# Board_Kabin_shematic.net
KiCad netlist of a schematic drawn in Altium Designer
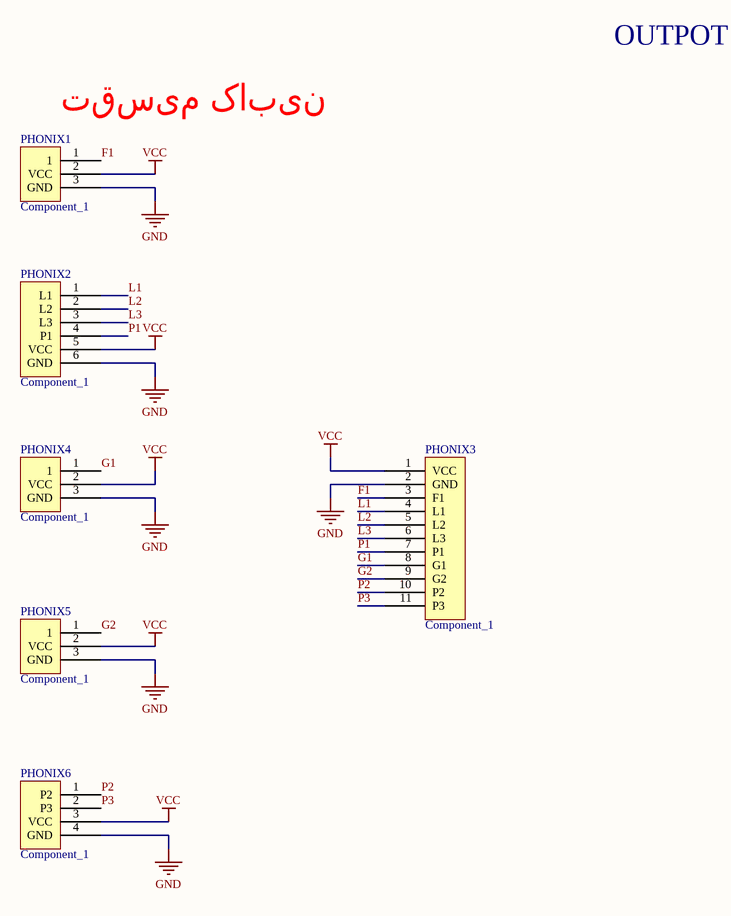
[diagram p0: Board_Kabin_shematic.SchDoc]

(export (version "E")
  (design (tool "Eeschema 10.0.6"))
  (components
    (comp (ref "PHONIX1")
      (value "Component_1")
      (footprint "PHONIX3")
      (description "PHONIX3PIN DIP")
      (libsource (lib "PHONIX3_SH") (part "Component_1"))
    )
    (comp (ref "PHONIX2")
      (value "Component_1")
      (footprint "PHONIX5")
      (libsource (lib "PHONIX6_SH") (part "Component_1"))
    )
    (comp (ref "PHONIX3")
      (value "Component_1")
      (footprint "PHONIX11")
      (description "PHONIX 11 PIN DIP")
      (libsource (lib "PHONIX11_SH") (part "Component_1"))
    )
    (comp (ref "PHONIX4")
      (value "Component_1")
      (footprint "PHONIX3")
      (description "PHONIX3PIN DIP")
      (libsource (lib "PHONIX3_SH") (part "Component_1"))
    )
    (comp (ref "PHONIX5")
      (value "Component_1")
      (footprint "PHONIX3")
      (description "PHONIX3PIN DIP")
      (libsource (lib "PHONIX3_SH") (part "Component_1"))
    )
    (comp (ref "PHONIX6")
      (value "Component_1")
      (footprint "PHONIX4")
      (libsource (lib "PHONIX4_SH") (part "Component_1"))
    )
  )
  (nets
    (net (code "1") (name "/F1") (class "Default")
      (node (ref "PHONIX1") (pin "1") (pinfunction "1_1") (pintype "passive"))
      (node (ref "PHONIX3") (pin "3") (pinfunction "F1_3") (pintype "passive"))
    )
    (net (code "2") (name "/G1") (class "Default")
      (node (ref "PHONIX3") (pin "8") (pinfunction "G1_8") (pintype "passive"))
      (node (ref "PHONIX4") (pin "1") (pinfunction "1_1") (pintype "passive"))
    )
    (net (code "3") (name "/G2") (class "Default")
      (node (ref "PHONIX3") (pin "9") (pinfunction "G2_9") (pintype "passive"))
      (node (ref "PHONIX5") (pin "1") (pinfunction "1_1") (pintype "passive"))
    )
    (net (code "4") (name "/L1") (class "Default")
      (node (ref "PHONIX2") (pin "1") (pinfunction "L1_1") (pintype "passive"))
      (node (ref "PHONIX3") (pin "4") (pinfunction "L1_4") (pintype "passive"))
    )
    (net (code "5") (name "/L2") (class "Default")
      (node (ref "PHONIX2") (pin "2") (pinfunction "L2_2") (pintype "passive"))
      (node (ref "PHONIX3") (pin "5") (pinfunction "L2_5") (pintype "passive"))
    )
    (net (code "6") (name "/L3") (class "Default")
      (node (ref "PHONIX2") (pin "3") (pinfunction "L3_3") (pintype "passive"))
      (node (ref "PHONIX3") (pin "6") (pinfunction "L3_6") (pintype "passive"))
    )
    (net (code "7") (name "/P1") (class "Default")
      (node (ref "PHONIX2") (pin "4") (pinfunction "P1_4") (pintype "passive"))
      (node (ref "PHONIX3") (pin "7") (pinfunction "P1_7") (pintype "passive"))
    )
    (net (code "8") (name "/P2") (class "Default")
      (node (ref "PHONIX3") (pin "10") (pinfunction "P2_10") (pintype "passive"))
      (node (ref "PHONIX6") (pin "1") (pinfunction "P2_1") (pintype "passive"))
    )
    (net (code "9") (name "/P3") (class "Default")
      (node (ref "PHONIX3") (pin "11") (pinfunction "P3_11") (pintype "passive"))
      (node (ref "PHONIX6") (pin "2") (pinfunction "P3_2") (pintype "passive"))
    )
    (net (code "10") (name "GND") (class "Default")
      (node (ref "PHONIX1") (pin "3") (pinfunction "GND_3") (pintype "passive"))
      (node (ref "PHONIX2") (pin "6") (pinfunction "GND_6") (pintype "passive"))
      (node (ref "PHONIX3") (pin "2") (pinfunction "GND_2") (pintype "passive"))
      (node (ref "PHONIX4") (pin "3") (pinfunction "GND_3") (pintype "passive"))
      (node (ref "PHONIX5") (pin "3") (pinfunction "GND_3") (pintype "passive"))
      (node (ref "PHONIX6") (pin "4") (pinfunction "GND_4") (pintype "passive"))
    )
    (net (code "11") (name "VCC") (class "Default")
      (node (ref "PHONIX1") (pin "2") (pinfunction "VCC_2") (pintype "passive"))
      (node (ref "PHONIX2") (pin "5") (pinfunction "VCC_5") (pintype "passive"))
      (node (ref "PHONIX3") (pin "1") (pinfunction "VCC_1") (pintype "passive"))
      (node (ref "PHONIX4") (pin "2") (pinfunction "VCC_2") (pintype "passive"))
      (node (ref "PHONIX5") (pin "2") (pinfunction "VCC_2") (pintype "passive"))
      (node (ref "PHONIX6") (pin "3") (pinfunction "VCC_3") (pintype "passive"))
    )
  )
)
